# Power_Board_DCIN.net
KiCad netlist of a schematic drawn in Altium Designer
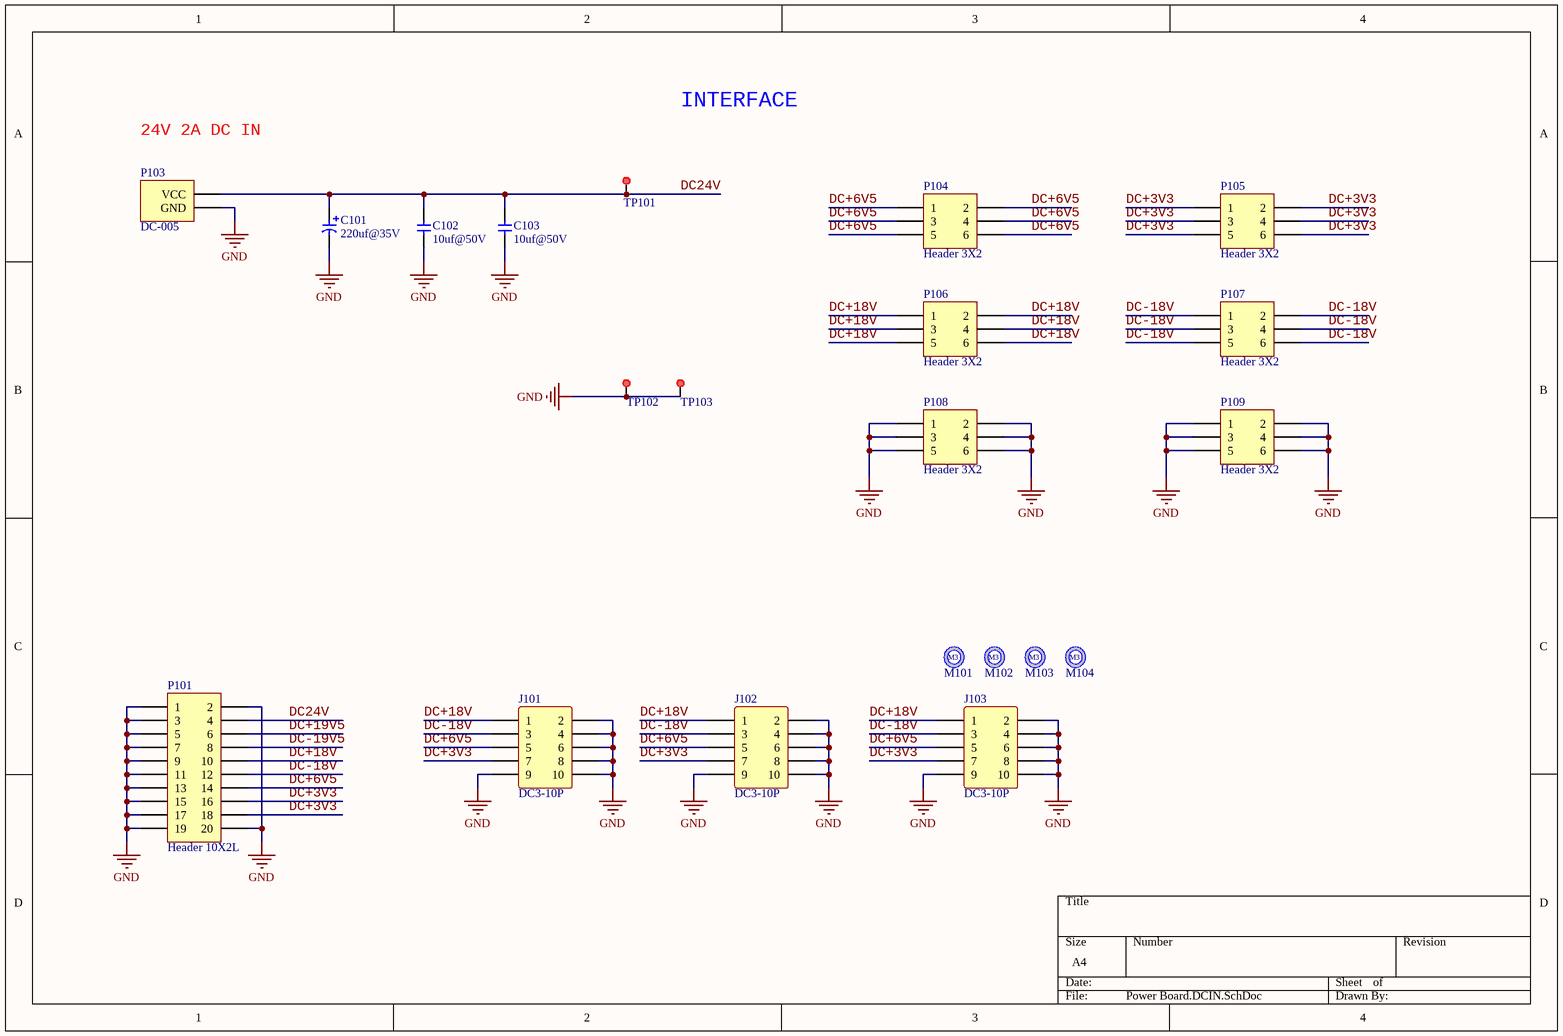
[diagram p0: Power Board.DCIN.SchDoc]

(export (version "E")
  (design (tool "Eeschema 10.0.6"))
  (components
    (comp (ref "C101")
      (value "220uf@35V")
      (footprint "C8X12")
      (fields (field (name "Comment") "Cap2"))
      (libsource (lib "carrot_lib") (part "Cap2"))
    )
    (comp (ref "C102")
      (value "10uf@50V")
      (footprint "C1206")
      (fields (field (name "Comment") "Cap"))
      (libsource (lib "carrot_lib") (part "Cap"))
    )
    (comp (ref "C103")
      (value "10uf@50V")
      (footprint "C1206")
      (fields (field (name "Comment") "Cap"))
      (libsource (lib "carrot_lib") (part "Cap"))
    )
    (comp (ref "J101")
      (value "DC3-10P")
      (footprint "DC3-10P")
      (libsource (lib "carrot_lib") (part "DC3-10P"))
    )
    (comp (ref "J102")
      (value "DC3-10P")
      (footprint "DC3-10P")
      (libsource (lib "carrot_lib") (part "DC3-10P"))
    )
    (comp (ref "J103")
      (value "DC3-10P")
      (footprint "DC3-10P")
      (libsource (lib "carrot_lib") (part "DC3-10P"))
    )
    (comp (ref "M101") (value "M3") (footprint "M3-3.2X5") (libsource (lib "carrot_lib") (part "M3")))
    (comp (ref "M102") (value "M3") (footprint "M3-3.2X5") (libsource (lib "carrot_lib") (part "M3")))
    (comp (ref "M103") (value "M3") (footprint "M3-3.2X5") (libsource (lib "carrot_lib") (part "M3")))
    (comp (ref "M104") (value "M3") (footprint "M3-3.2X5") (libsource (lib "carrot_lib") (part "M3")))
    (comp (ref "P101")
      (value "Header 10X2L")
      (footprint "HDR2X10LML")
      (description "Header, 10-Pin, Dual row, Pin 1 on Left")
      (libsource (lib "carrot_lib") (part "Header 10X2L"))
    )
    (comp (ref "P103") (value "DC-005") (footprint "DC-005") (libsource (lib "carrot_lib") (part "DC-005")))
    (comp (ref "P104")
      (value "Header 3X2")
      (footprint "HDR2X3")
      (description "Header, 3-Pin, Dual row")
      (libsource (lib "carrot_lib") (part "Header 3X2"))
    )
    (comp (ref "P105")
      (value "Header 3X2")
      (footprint "HDR2X3")
      (description "Header, 3-Pin, Dual row")
      (libsource (lib "carrot_lib") (part "Header 3X2"))
    )
    (comp (ref "P106")
      (value "Header 3X2")
      (footprint "HDR2X3")
      (description "Header, 3-Pin, Dual row")
      (libsource (lib "carrot_lib") (part "Header 3X2"))
    )
    (comp (ref "P107")
      (value "Header 3X2")
      (footprint "HDR2X3")
      (description "Header, 3-Pin, Dual row")
      (libsource (lib "carrot_lib") (part "Header 3X2"))
    )
    (comp (ref "P108")
      (value "Header 3X2")
      (footprint "HDR2X3")
      (description "Header, 3-Pin, Dual row")
      (libsource (lib "carrot_lib") (part "Header 3X2"))
    )
    (comp (ref "P109")
      (value "Header 3X2")
      (footprint "HDR2X3")
      (description "Header, 3-Pin, Dual row")
      (libsource (lib "carrot_lib") (part "Header 3X2"))
    )
    (comp (ref "TP101")
      (value "TestPoint")
      (footprint "TestPoint-THM1.0-L")
      (description "测试点")
      (libsource (lib "carrot_lib") (part "TestPoint"))
    )
    (comp (ref "TP102")
      (value "TestPoint")
      (footprint "TestPoint-THM1.0-L")
      (description "测试点")
      (libsource (lib "carrot_lib") (part "TestPoint"))
    )
    (comp (ref "TP103")
      (value "TestPoint")
      (footprint "TestPoint-THM1.0-L")
      (description "测试点")
      (libsource (lib "carrot_lib") (part "TestPoint"))
    )
  )
  (nets
    (net (code "1") (name "/DC+3V3") (class "Default")
      (node (ref "J101") (pin "7") (pinfunction "7_7") (pintype "passive"))
      (node (ref "J102") (pin "7") (pinfunction "7_7") (pintype "passive"))
      (node (ref "J103") (pin "7") (pinfunction "7_7") (pintype "passive"))
      (node (ref "P101") (pin "16") (pinfunction "16_16") (pintype "passive"))
      (node (ref "P101") (pin "18") (pinfunction "18_18") (pintype "passive"))
      (node (ref "P105") (pin "1") (pinfunction "1_1") (pintype "passive"))
      (node (ref "P105") (pin "2") (pinfunction "2_2") (pintype "passive"))
      (node (ref "P105") (pin "3") (pinfunction "3_3") (pintype "passive"))
      (node (ref "P105") (pin "4") (pinfunction "4_4") (pintype "passive"))
      (node (ref "P105") (pin "5") (pinfunction "5_5") (pintype "passive"))
      (node (ref "P105") (pin "6") (pinfunction "6_6") (pintype "passive"))
    )
    (net (code "2") (name "/DC+6V5") (class "Default")
      (node (ref "J101") (pin "5") (pinfunction "5_5") (pintype "passive"))
      (node (ref "J102") (pin "5") (pinfunction "5_5") (pintype "passive"))
      (node (ref "J103") (pin "5") (pinfunction "5_5") (pintype "passive"))
      (node (ref "P101") (pin "14") (pinfunction "14_14") (pintype "passive"))
      (node (ref "P104") (pin "1") (pinfunction "1_1") (pintype "passive"))
      (node (ref "P104") (pin "2") (pinfunction "2_2") (pintype "passive"))
      (node (ref "P104") (pin "3") (pinfunction "3_3") (pintype "passive"))
      (node (ref "P104") (pin "4") (pinfunction "4_4") (pintype "passive"))
      (node (ref "P104") (pin "5") (pinfunction "5_5") (pintype "passive"))
      (node (ref "P104") (pin "6") (pinfunction "6_6") (pintype "passive"))
    )
    (net (code "3") (name "/DC+18V") (class "Default")
      (node (ref "J101") (pin "1") (pinfunction "1_1") (pintype "passive"))
      (node (ref "J102") (pin "1") (pinfunction "1_1") (pintype "passive"))
      (node (ref "J103") (pin "1") (pinfunction "1_1") (pintype "passive"))
      (node (ref "P101") (pin "10") (pinfunction "10_10") (pintype "passive"))
      (node (ref "P106") (pin "1") (pinfunction "1_1") (pintype "passive"))
      (node (ref "P106") (pin "2") (pinfunction "2_2") (pintype "passive"))
      (node (ref "P106") (pin "3") (pinfunction "3_3") (pintype "passive"))
      (node (ref "P106") (pin "4") (pinfunction "4_4") (pintype "passive"))
      (node (ref "P106") (pin "5") (pinfunction "5_5") (pintype "passive"))
      (node (ref "P106") (pin "6") (pinfunction "6_6") (pintype "passive"))
    )
    (net (code "4") (name "/DC+19V5") (class "Default")
      (node (ref "P101") (pin "6") (pinfunction "6_6") (pintype "passive"))
    )
    (net (code "5") (name "/DC-18V") (class "Default")
      (node (ref "J101") (pin "3") (pinfunction "3_3") (pintype "passive"))
      (node (ref "J102") (pin "3") (pinfunction "3_3") (pintype "passive"))
      (node (ref "J103") (pin "3") (pinfunction "3_3") (pintype "passive"))
      (node (ref "P101") (pin "12") (pinfunction "12_12") (pintype "passive"))
      (node (ref "P107") (pin "1") (pinfunction "1_1") (pintype "passive"))
      (node (ref "P107") (pin "2") (pinfunction "2_2") (pintype "passive"))
      (node (ref "P107") (pin "3") (pinfunction "3_3") (pintype "passive"))
      (node (ref "P107") (pin "4") (pinfunction "4_4") (pintype "passive"))
      (node (ref "P107") (pin "5") (pinfunction "5_5") (pintype "passive"))
      (node (ref "P107") (pin "6") (pinfunction "6_6") (pintype "passive"))
    )
    (net (code "6") (name "/DC-19V5") (class "Default")
      (node (ref "P101") (pin "8") (pinfunction "8_8") (pintype "passive"))
    )
    (net (code "7") (name "/DC24V") (class "Default")
      (node (ref "C101") (pin "1") (pinfunction "1_1") (pintype "passive"))
      (node (ref "C102") (pin "2") (pinfunction "2_2") (pintype "passive"))
      (node (ref "C103") (pin "2") (pinfunction "2_2") (pintype "passive"))
      (node (ref "P101") (pin "4") (pinfunction "4_4") (pintype "passive"))
      (node (ref "P103") (pin "1") (pinfunction "VCC_1") (pintype "passive"))
      (node (ref "TP101") (pin "1") (pinfunction "1_1") (pintype "passive"))
    )
    (net (code "8") (name "GND") (class "Default")
      (node (ref "C101") (pin "2") (pinfunction "2_2") (pintype "passive"))
      (node (ref "C102") (pin "1") (pinfunction "1_1") (pintype "passive"))
      (node (ref "C103") (pin "1") (pinfunction "1_1") (pintype "passive"))
      (node (ref "J101") (pin "10") (pinfunction "10_10") (pintype "passive"))
      (node (ref "J101") (pin "2") (pinfunction "2_2") (pintype "passive"))
      (node (ref "J101") (pin "4") (pinfunction "4_4") (pintype "passive"))
      (node (ref "J101") (pin "6") (pinfunction "6_6") (pintype "passive"))
      (node (ref "J101") (pin "8") (pinfunction "8_8") (pintype "passive"))
      (node (ref "J101") (pin "9") (pinfunction "9_9") (pintype "passive"))
      (node (ref "J102") (pin "10") (pinfunction "10_10") (pintype "passive"))
      (node (ref "J102") (pin "2") (pinfunction "2_2") (pintype "passive"))
      (node (ref "J102") (pin "4") (pinfunction "4_4") (pintype "passive"))
      (node (ref "J102") (pin "6") (pinfunction "6_6") (pintype "passive"))
      (node (ref "J102") (pin "8") (pinfunction "8_8") (pintype "passive"))
      (node (ref "J102") (pin "9") (pinfunction "9_9") (pintype "passive"))
      (node (ref "J103") (pin "10") (pinfunction "10_10") (pintype "passive"))
      (node (ref "J103") (pin "2") (pinfunction "2_2") (pintype "passive"))
      (node (ref "J103") (pin "4") (pinfunction "4_4") (pintype "passive"))
      (node (ref "J103") (pin "6") (pinfunction "6_6") (pintype "passive"))
      (node (ref "J103") (pin "8") (pinfunction "8_8") (pintype "passive"))
      (node (ref "J103") (pin "9") (pinfunction "9_9") (pintype "passive"))
      (node (ref "P101") (pin "1") (pinfunction "1_1") (pintype "passive"))
      (node (ref "P101") (pin "11") (pinfunction "11_11") (pintype "passive"))
      (node (ref "P101") (pin "13") (pinfunction "13_13") (pintype "passive"))
      (node (ref "P101") (pin "15") (pinfunction "15_15") (pintype "passive"))
      (node (ref "P101") (pin "17") (pinfunction "17_17") (pintype "passive"))
      (node (ref "P101") (pin "19") (pinfunction "19_19") (pintype "passive"))
      (node (ref "P101") (pin "2") (pinfunction "2_2") (pintype "passive"))
      (node (ref "P101") (pin "20") (pinfunction "20_20") (pintype "passive"))
      (node (ref "P101") (pin "3") (pinfunction "3_3") (pintype "passive"))
      (node (ref "P101") (pin "5") (pinfunction "5_5") (pintype "passive"))
      (node (ref "P101") (pin "7") (pinfunction "7_7") (pintype "passive"))
      (node (ref "P101") (pin "9") (pinfunction "9_9") (pintype "passive"))
      (node (ref "P103") (pin "2") (pinfunction "GND_2") (pintype "passive"))
      (node (ref "P108") (pin "1") (pinfunction "1_1") (pintype "passive"))
      (node (ref "P108") (pin "2") (pinfunction "2_2") (pintype "passive"))
      (node (ref "P108") (pin "3") (pinfunction "3_3") (pintype "passive"))
      (node (ref "P108") (pin "4") (pinfunction "4_4") (pintype "passive"))
      (node (ref "P108") (pin "5") (pinfunction "5_5") (pintype "passive"))
      (node (ref "P108") (pin "6") (pinfunction "6_6") (pintype "passive"))
      (node (ref "P109") (pin "1") (pinfunction "1_1") (pintype "passive"))
      (node (ref "P109") (pin "2") (pinfunction "2_2") (pintype "passive"))
      (node (ref "P109") (pin "3") (pinfunction "3_3") (pintype "passive"))
      (node (ref "P109") (pin "4") (pinfunction "4_4") (pintype "passive"))
      (node (ref "P109") (pin "5") (pinfunction "5_5") (pintype "passive"))
      (node (ref "P109") (pin "6") (pinfunction "6_6") (pintype "passive"))
      (node (ref "TP102") (pin "1") (pinfunction "1_1") (pintype "passive"))
      (node (ref "TP103") (pin "1") (pinfunction "1_1") (pintype "passive"))
    )
  )
)
